# PowerSupply.net
KiCad netlist of a schematic drawn in Altium Designer
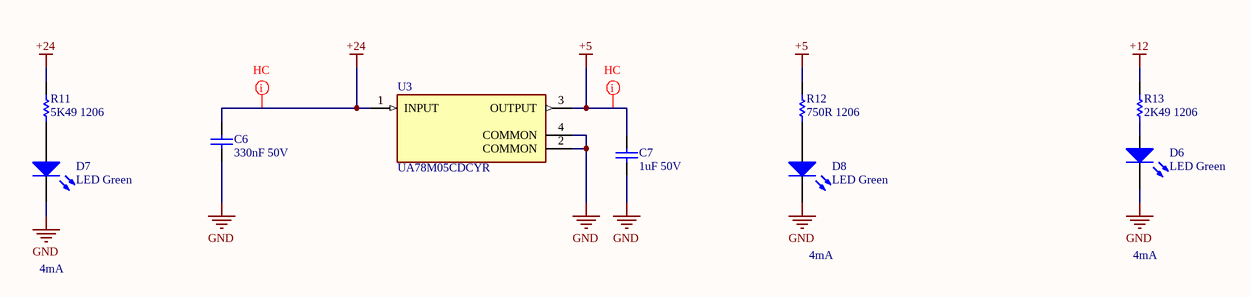
[diagram p0: PowerSupply.SchDoc]

(export (version "E")
  (design (tool "Eeschema 10.0.6"))
  (components
    (comp (ref "C6")
      (value "330nF 50V")
      (footprint "CAPC0603(1608)100_L")
      (description "CAP 330nF 35V ±10% 0603 (1608 Metric) Thickness 1mm SMD")
      (fields (field (name "TOLERANCE") "Â±10%"))
      (libsource (lib "Altium Content Vault") (part "CAP"))
    )
    (comp (ref "C7")
      (value "1uF 50V")
      (footprint "CAPC0603(1608)100_L")
      (description "CAP 1uF 35V ±10% 0603 (1608 Metric) Thickness 1mm SMD")
      (fields (field (name "TOLERANCE") "Â±10%"))
      (libsource (lib "Altium Content Vault") (part "CAP"))
    )
    (comp (ref "D6")
      (value "LED Green")
      (footprint "0603_A")
      (description "SMD mono-color Chip LED, WL-SMCW, Green")
      (fields (field (name "PARTNUMBER") "150060GS75000") (field (name "MANUFACTURER") "Wuerth Elektronik"))
      (libsource (lib "Altium Content Vault") (part "WE-LED_K1A2-2"))
    )
    (comp (ref "D7")
      (value "LED Green")
      (footprint "0603_A")
      (description "SMD mono-color Chip LED, WL-SMCW, Green")
      (fields (field (name "PARTNUMBER") "150060GS75000") (field (name "MANUFACTURER") "Wuerth Elektronik"))
      (libsource (lib "Altium Content Vault") (part "WE-LED_K1A2-2"))
    )
    (comp (ref "D8")
      (value "LED Green")
      (footprint "0603_A")
      (description "SMD mono-color Chip LED, WL-SMCW, Green")
      (fields (field (name "PARTNUMBER") "150060GS75000") (field (name "MANUFACTURER") "Wuerth Elektronik"))
      (libsource (lib "Altium Content Vault") (part "WE-LED_K1A2-2"))
    )
    (comp (ref "R11")
      (value "5K49 1206")
      (footprint "R-1206")
      (description "0.25W 1206")
      (fields (field (name "POWER") "0.1 W") (field (name "TOLERANCE") "1 %"))
      (libsource (lib "Schlib1") (part "R-1206"))
    )
    (comp (ref "R12")
      (value "750R 1206")
      (footprint "R-1206")
      (description "0.25W 1206")
      (fields (field (name "POWER") "0.1 W") (field (name "TOLERANCE") "1 %"))
      (libsource (lib "Schlib1") (part "R-1206"))
    )
    (comp (ref "R13")
      (value "2K49 1206")
      (footprint "R-1206")
      (description "0.25W 1206")
      (fields (field (name "POWER") "0.1 W") (field (name "TOLERANCE") "1 %"))
      (libsource (lib "Schlib1") (part "R-1206"))
    )
    (comp (ref "U3")
      (value "UA78M05CDCYR")
      (footprint "FP-DCY0004A-MFG")
      (description "IC REG LINEAR 5V 500MA SOT223-4")
      (fields
        (field (name "OCTOPART") "https://octopart.com/ua78m05cdcyr-texas+instruments-525243")
        (field (name "MANUFACTURER") "Texas Instruments")
      )
      (libsource (lib "Altium Content Vault") (part "94856b1f28d1528c32b2fce4634c7e4"))
    )
  )
  (nets
    (net (code "1") (name "+5") (class "Default")
      (node (ref "C7") (pin "1") (pinfunction "1_1") (pintype "passive"))
      (node (ref "R12") (pin "2") (pinfunction "2_2") (pintype "passive"))
      (node (ref "U3") (pin "3") (pinfunction "OUTPUT_3") (pintype "output"))
    )
    (net (code "2") (name "+12") (class "Default")
      (node (ref "R13") (pin "2") (pinfunction "2_2") (pintype "passive"))
    )
    (net (code "3") (name "+24") (class "Default")
      (node (ref "C6") (pin "2") (pinfunction "2_2") (pintype "passive"))
      (node (ref "R11") (pin "2") (pinfunction "2_2") (pintype "passive"))
      (node (ref "U3") (pin "1") (pinfunction "INPUT_1") (pintype "input"))
    )
    (net (code "4") (name "GND") (class "Default")
      (node (ref "C6") (pin "1") (pinfunction "1_1") (pintype "passive"))
      (node (ref "C7") (pin "2") (pinfunction "2_2") (pintype "passive"))
      (node (ref "D6") (pin "1") (pinfunction "K_1") (pintype "passive"))
      (node (ref "D7") (pin "1") (pinfunction "K_1") (pintype "passive"))
      (node (ref "D8") (pin "1") (pinfunction "K_1") (pintype "passive"))
      (node (ref "U3") (pin "2") (pinfunction "COMMON_2") (pintype "power_in"))
      (node (ref "U3") (pin "4") (pinfunction "COMMON_4") (pintype "power_in"))
    )
    (net (code "5") (name "Net-(D6-A)") (class "Default")
      (node (ref "D6") (pin "2") (pinfunction "A_2") (pintype "passive"))
      (node (ref "R13") (pin "1") (pinfunction "1_1") (pintype "passive"))
    )
    (net (code "6") (name "Net-(D7-A)") (class "Default")
      (node (ref "D7") (pin "2") (pinfunction "A_2") (pintype "passive"))
      (node (ref "R11") (pin "1") (pinfunction "1_1") (pintype "passive"))
    )
    (net (code "7") (name "Net-(D8-A)") (class "Default")
      (node (ref "D8") (pin "2") (pinfunction "A_2") (pintype "passive"))
      (node (ref "R12") (pin "1") (pinfunction "1_1") (pintype "passive"))
    )
  )
)
